# TT_PulseGen_V1_0.net
KiCad netlist of a schematic drawn in EAGLE
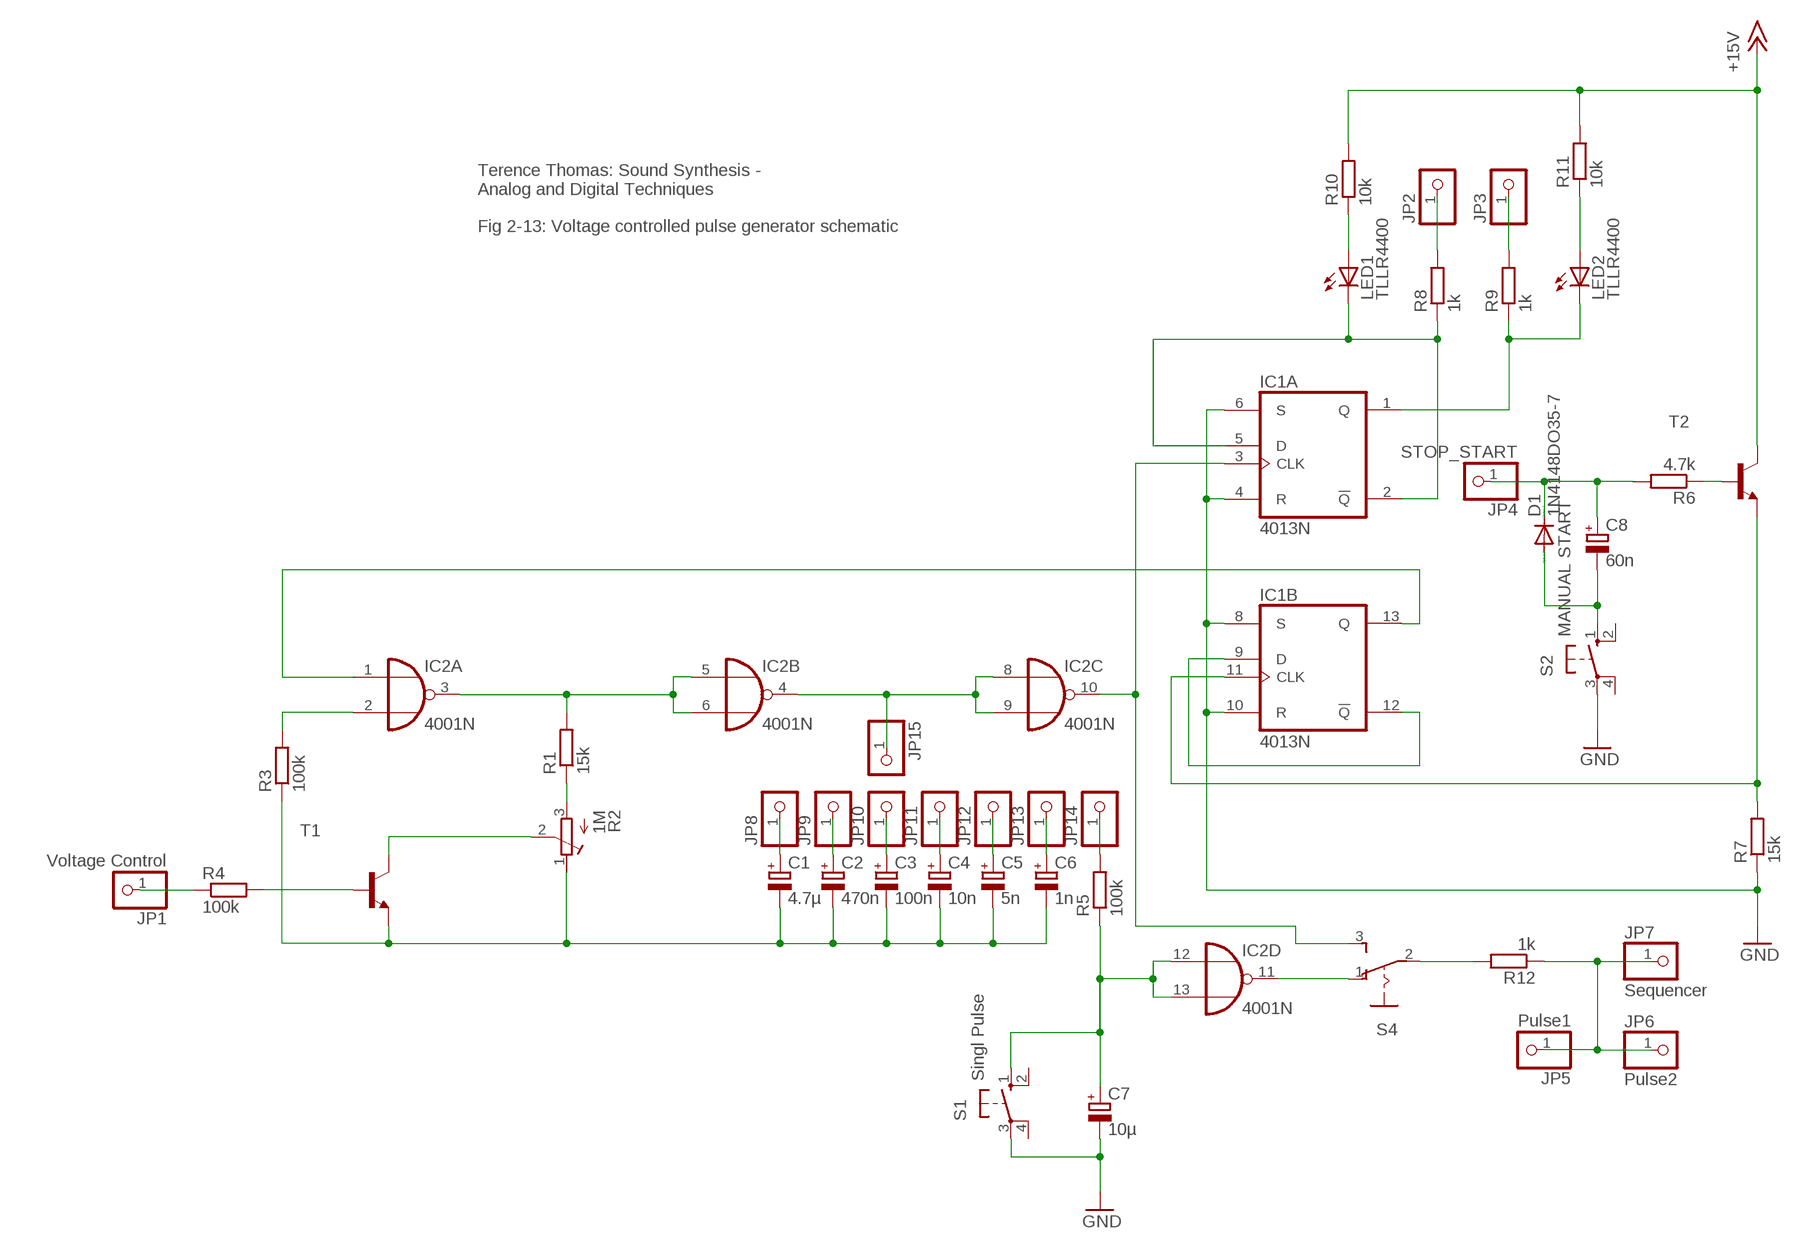
[diagram p0: schematic, sheet 1]

(export (version "E")
  (design (tool "Eeschema 10.0.6"))
  (components
    (comp (ref "C1")
      (value "4.7µ")
      (footprint "eagle-import:E2,5-5")
      (libsource (lib "eagle-import") (part "CPOL-EUE2.5-5"))
    )
    (comp (ref "C2")
      (value "470n")
      (footprint "eagle-import:E2,5-5")
      (libsource (lib "eagle-import") (part "CPOL-EUE2.5-5"))
    )
    (comp (ref "C3")
      (value "100n")
      (footprint "eagle-import:E2,5-5")
      (libsource (lib "eagle-import") (part "CPOL-EUE2.5-5"))
    )
    (comp (ref "C4")
      (value "10n")
      (footprint "eagle-import:E2,5-5")
      (libsource (lib "eagle-import") (part "CPOL-EUE2.5-5"))
    )
    (comp (ref "C5")
      (value "5n")
      (footprint "eagle-import:E2,5-5")
      (libsource (lib "eagle-import") (part "CPOL-EUE2.5-5"))
    )
    (comp (ref "C6")
      (value "1n")
      (footprint "eagle-import:E2,5-5")
      (libsource (lib "eagle-import") (part "CPOL-EUE2.5-5"))
    )
    (comp (ref "C7")
      (value "10µ")
      (footprint "eagle-import:E2,5-5")
      (libsource (lib "eagle-import") (part "CPOL-EUE2.5-5"))
    )
    (comp (ref "C8")
      (value "60n")
      (footprint "eagle-import:E2,5-5")
      (libsource (lib "eagle-import") (part "CPOL-EUE2.5-5"))
    )
    (comp (ref "D1")
      (value "1N4148DO35-7")
      (footprint "eagle-import:DO35-7")
      (libsource (lib "eagle-import") (part "1N4148DO35-7"))
    )
    (comp (ref "IC1")
      (value "4013N")
      (footprint "eagle-import:DIL14")
      (libsource (lib "eagle-import") (part "4013N"))
    )
    (comp (ref "IC2")
      (value "4001N")
      (footprint "eagle-import:DIL14")
      (libsource (lib "eagle-import") (part "4001N"))
    )
    (comp (ref "JP1")
      (value "Voltage Control")
      (footprint "eagle-import:1X01")
      (libsource (lib "eagle-import") (part "PINHD-1X1"))
    )
    (comp (ref "JP2")
      (value "PINHD-1X1")
      (footprint "eagle-import:1X01")
      (libsource (lib "eagle-import") (part "PINHD-1X1"))
    )
    (comp (ref "JP3")
      (value "PINHD-1X1")
      (footprint "eagle-import:1X01")
      (libsource (lib "eagle-import") (part "PINHD-1X1"))
    )
    (comp (ref "JP4")
      (value "STOP_START")
      (footprint "eagle-import:1X01")
      (libsource (lib "eagle-import") (part "PINHD-1X1"))
    )
    (comp (ref "JP5")
      (value "Pulse1")
      (footprint "eagle-import:1X01")
      (libsource (lib "eagle-import") (part "PINHD-1X1"))
    )
    (comp (ref "JP6")
      (value "Pulse2")
      (footprint "eagle-import:1X01")
      (libsource (lib "eagle-import") (part "PINHD-1X1"))
    )
    (comp (ref "JP7")
      (value "Sequencer")
      (footprint "eagle-import:1X01")
      (libsource (lib "eagle-import") (part "PINHD-1X1"))
    )
    (comp (ref "JP8")
      (value "PINHD-1X1")
      (footprint "eagle-import:1X01")
      (libsource (lib "eagle-import") (part "PINHD-1X1"))
    )
    (comp (ref "JP9")
      (value "PINHD-1X1")
      (footprint "eagle-import:1X01")
      (libsource (lib "eagle-import") (part "PINHD-1X1"))
    )
    (comp (ref "JP10")
      (value "PINHD-1X1")
      (footprint "eagle-import:1X01")
      (libsource (lib "eagle-import") (part "PINHD-1X1"))
    )
    (comp (ref "JP11")
      (value "PINHD-1X1")
      (footprint "eagle-import:1X01")
      (libsource (lib "eagle-import") (part "PINHD-1X1"))
    )
    (comp (ref "JP12")
      (value "PINHD-1X1")
      (footprint "eagle-import:1X01")
      (libsource (lib "eagle-import") (part "PINHD-1X1"))
    )
    (comp (ref "JP13")
      (value "PINHD-1X1")
      (footprint "eagle-import:1X01")
      (libsource (lib "eagle-import") (part "PINHD-1X1"))
    )
    (comp (ref "JP14")
      (value "PINHD-1X1")
      (footprint "eagle-import:1X01")
      (libsource (lib "eagle-import") (part "PINHD-1X1"))
    )
    (comp (ref "JP15")
      (value "PINHD-1X1")
      (footprint "eagle-import:1X01")
      (libsource (lib "eagle-import") (part "PINHD-1X1"))
    )
    (comp (ref "LED1")
      (value "TLLR4400")
      (footprint "eagle-import:LED3MM")
      (fields (field (name "MF") "VISHAY SEMICONDUCTOR"))
      (libsource (lib "eagle-import") (part "TLLR4400"))
    )
    (comp (ref "LED2")
      (value "TLLR4400")
      (footprint "eagle-import:LED3MM")
      (fields (field (name "MF") "VISHAY SEMICONDUCTOR"))
      (libsource (lib "eagle-import") (part "TLLR4400"))
    )
    (comp (ref "R1")
      (value "15k")
      (footprint "eagle-import:0204_7")
      (libsource (lib "eagle-import") (part "R-EU_0204/7"))
    )
    (comp (ref "R2")
      (value "1M")
      (footprint "eagle-import:RTRIMT93YA")
      (libsource (lib "eagle-import") (part "R-TRIMMT93YA"))
    )
    (comp (ref "R3")
      (value "100k")
      (footprint "eagle-import:0204_7")
      (libsource (lib "eagle-import") (part "R-EU_0204/7"))
    )
    (comp (ref "R4")
      (value "100k")
      (footprint "eagle-import:0204_7")
      (libsource (lib "eagle-import") (part "R-EU_0204/7"))
    )
    (comp (ref "R5")
      (value "100k")
      (footprint "eagle-import:0204_7")
      (libsource (lib "eagle-import") (part "R-EU_0204/7"))
    )
    (comp (ref "R6")
      (value "4.7k")
      (footprint "eagle-import:0204_7")
      (libsource (lib "eagle-import") (part "R-EU_0204/7"))
    )
    (comp (ref "R7")
      (value "15k")
      (footprint "eagle-import:0204_7")
      (libsource (lib "eagle-import") (part "R-EU_0204/7"))
    )
    (comp (ref "R8")
      (value "1k")
      (footprint "eagle-import:0204_7")
      (libsource (lib "eagle-import") (part "R-EU_0204/7"))
    )
    (comp (ref "R9")
      (value "1k")
      (footprint "eagle-import:0204_7")
      (libsource (lib "eagle-import") (part "R-EU_0204/7"))
    )
    (comp (ref "R10")
      (value "10k")
      (footprint "eagle-import:0204_7")
      (libsource (lib "eagle-import") (part "R-EU_0204/7"))
    )
    (comp (ref "R11")
      (value "10k")
      (footprint "eagle-import:0204_7")
      (libsource (lib "eagle-import") (part "R-EU_0204/7"))
    )
    (comp (ref "R12")
      (value "1k")
      (footprint "eagle-import:0204_7")
      (libsource (lib "eagle-import") (part "R-EU_0204/7"))
    )
    (comp (ref "S1")
      (value "Singl Pulse")
      (footprint "eagle-import:B3F-10XX")
      (fields (field (name "MPN") "B3F-1000"))
      (libsource (lib "eagle-import") (part "10-XX"))
    )
    (comp (ref "S2")
      (value "MANUAL START")
      (footprint "eagle-import:B3F-10XX")
      (fields (field (name "MPN") "B3F-1000"))
      (libsource (lib "eagle-import") (part "10-XX"))
    )
    (comp (ref "S4")
      (value "255SB")
      (footprint "eagle-import:255SB")
      (libsource (lib "eagle-import") (part "255SB"))
    )
    (comp (ref "T1")
      (value "-NPN-TO92-EBC")
      (footprint "eagle-import:TO92-EBC")
      (libsource (lib "eagle-import") (part "-NPN-TO92-EBC"))
    )
    (comp (ref "T2")
      (value "-NPN-TO92-EBC")
      (footprint "eagle-import:TO92-EBC")
      (libsource (lib "eagle-import") (part "-NPN-TO92-EBC"))
    )
  )
  (nets
    (net (code "1") (name "+15V") (class "Default")
      (node (ref "R10") (pin "2") (pinfunction "2_2") (pintype "passive"))
      (node (ref "R11") (pin "2") (pinfunction "2_2") (pintype "passive"))
      (node (ref "T2") (pin "C") (pinfunction "C_C") (pintype "passive"))
    )
    (net (code "2") (name "GND") (class "Default")
      (node (ref "C7") (pin "-") (pinfunction "-_-") (pintype "passive"))
      (node (ref "IC1") (pin "10") (pinfunction "R_10") (pintype "input"))
      (node (ref "IC1") (pin "4") (pinfunction "R_4") (pintype "input"))
      (node (ref "IC1") (pin "6") (pinfunction "S_6") (pintype "input"))
      (node (ref "IC1") (pin "8") (pinfunction "S_8") (pintype "input"))
      (node (ref "R7") (pin "1") (pinfunction "1_1") (pintype "passive"))
      (node (ref "S1") (pin "3") (pinfunction "P_3") (pintype "passive"))
      (node (ref "S2") (pin "3") (pinfunction "P_3") (pintype "passive"))
    )
    (net (code "3") (name "Net-(C1-Pad+)") (class "Default")
      (node (ref "C1") (pin "+") (pinfunction "+_+") (pintype "passive"))
      (node (ref "JP8") (pin "1") (pinfunction "1_1") (pintype "passive"))
    )
    (net (code "4") (name "Net-(C2-Pad+)") (class "Default")
      (node (ref "C2") (pin "+") (pinfunction "+_+") (pintype "passive"))
      (node (ref "JP9") (pin "1") (pinfunction "1_1") (pintype "passive"))
    )
    (net (code "5") (name "Net-(C3-Pad+)") (class "Default")
      (node (ref "C3") (pin "+") (pinfunction "+_+") (pintype "passive"))
      (node (ref "JP10") (pin "1") (pinfunction "1_1") (pintype "passive"))
    )
    (net (code "6") (name "Net-(C4-Pad+)") (class "Default")
      (node (ref "C4") (pin "+") (pinfunction "+_+") (pintype "passive"))
      (node (ref "JP11") (pin "1") (pinfunction "1_1") (pintype "passive"))
    )
    (net (code "7") (name "Net-(C5-Pad+)") (class "Default")
      (node (ref "C5") (pin "+") (pinfunction "+_+") (pintype "passive"))
      (node (ref "JP12") (pin "1") (pinfunction "1_1") (pintype "passive"))
    )
    (net (code "8") (name "Net-(C6-Pad+)") (class "Default")
      (node (ref "C6") (pin "+") (pinfunction "+_+") (pintype "passive"))
      (node (ref "JP13") (pin "1") (pinfunction "1_1") (pintype "passive"))
    )
    (net (code "9") (name "Net-(C8-Pad+)") (class "Default")
      (node (ref "C8") (pin "+") (pinfunction "+_+") (pintype "passive"))
      (node (ref "D1") (pin "C") (pinfunction "C_C") (pintype "passive"))
      (node (ref "JP4") (pin "1") (pinfunction "1_1") (pintype "passive"))
      (node (ref "R6") (pin "2") (pinfunction "2_2") (pintype "passive"))
    )
    (net (code "10") (name "Net-(IC1A-CLK)") (class "Default")
      (node (ref "IC1") (pin "3") (pinfunction "CLK_3") (pintype "input"))
      (node (ref "IC2") (pin "10") (pinfunction "O_10") (pintype "output"))
      (node (ref "S4") (pin "3") (pinfunction "S_3") (pintype "passive"))
    )
    (net (code "11") (name "Net-(IC1A-D)") (class "Default")
      (node (ref "IC1") (pin "2") (pinfunction "~{Q}_2") (pintype "output"))
      (node (ref "IC1") (pin "5") (pinfunction "D_5") (pintype "input"))
      (node (ref "LED1") (pin "K") (pinfunction "C_K") (pintype "passive"))
      (node (ref "R8") (pin "1") (pinfunction "1_1") (pintype "passive"))
    )
    (net (code "12") (name "Net-(IC1A-Q)") (class "Default")
      (node (ref "IC1") (pin "1") (pinfunction "Q_1") (pintype "output"))
      (node (ref "LED2") (pin "K") (pinfunction "C_K") (pintype "passive"))
      (node (ref "R9") (pin "1") (pinfunction "1_1") (pintype "passive"))
    )
    (net (code "13") (name "Net-(IC1B-CLK)") (class "Default")
      (node (ref "IC1") (pin "11") (pinfunction "CLK_11") (pintype "input"))
      (node (ref "R7") (pin "2") (pinfunction "2_2") (pintype "passive"))
      (node (ref "T2") (pin "E") (pinfunction "E_E") (pintype "passive"))
    )
    (net (code "14") (name "Net-(IC1B-D)") (class "Default")
      (node (ref "IC1") (pin "12") (pinfunction "~{Q}_12") (pintype "output"))
      (node (ref "IC1") (pin "9") (pinfunction "D_9") (pintype "input"))
    )
    (net (code "15") (name "Net-(IC1B-Q)") (class "Default")
      (node (ref "IC1") (pin "13") (pinfunction "Q_13") (pintype "output"))
      (node (ref "IC2") (pin "1") (pinfunction "I0_1") (pintype "input"))
    )
    (net (code "16") (name "Net-(IC2A-I1)") (class "Default")
      (node (ref "IC2") (pin "2") (pinfunction "I1_2") (pintype "input"))
      (node (ref "R3") (pin "2") (pinfunction "2_2") (pintype "passive"))
    )
    (net (code "17") (name "Net-(IC2A-O)") (class "Default")
      (node (ref "IC2") (pin "3") (pinfunction "O_3") (pintype "output"))
      (node (ref "IC2") (pin "5") (pinfunction "I0_5") (pintype "input"))
      (node (ref "IC2") (pin "6") (pinfunction "I1_6") (pintype "input"))
      (node (ref "R1") (pin "2") (pinfunction "2_2") (pintype "passive"))
    )
    (net (code "18") (name "Net-(IC2B-O)") (class "Default")
      (node (ref "IC2") (pin "4") (pinfunction "O_4") (pintype "output"))
      (node (ref "IC2") (pin "8") (pinfunction "I0_8") (pintype "input"))
      (node (ref "IC2") (pin "9") (pinfunction "I1_9") (pintype "input"))
      (node (ref "JP15") (pin "1") (pinfunction "1_1") (pintype "passive"))
    )
    (net (code "19") (name "Net-(IC2D-I0)") (class "Default")
      (node (ref "C7") (pin "+") (pinfunction "+_+") (pintype "passive"))
      (node (ref "IC2") (pin "12") (pinfunction "I0_12") (pintype "input"))
      (node (ref "IC2") (pin "13") (pinfunction "I1_13") (pintype "input"))
      (node (ref "R5") (pin "1") (pinfunction "1_1") (pintype "passive"))
      (node (ref "S1") (pin "1") (pinfunction "S_1") (pintype "passive"))
    )
    (net (code "20") (name "Net-(IC2D-O)") (class "Default")
      (node (ref "IC2") (pin "11") (pinfunction "O_11") (pintype "output"))
      (node (ref "S4") (pin "1") (pinfunction "O_1") (pintype "passive"))
    )
    (net (code "21") (name "Net-(JP1-Pad1)") (class "Default")
      (node (ref "JP1") (pin "1") (pinfunction "1_1") (pintype "passive"))
      (node (ref "R4") (pin "1") (pinfunction "1_1") (pintype "passive"))
    )
    (net (code "22") (name "Net-(JP2-Pad1)") (class "Default")
      (node (ref "JP2") (pin "1") (pinfunction "1_1") (pintype "passive"))
      (node (ref "R8") (pin "2") (pinfunction "2_2") (pintype "passive"))
    )
    (net (code "23") (name "Net-(JP3-Pad1)") (class "Default")
      (node (ref "JP3") (pin "1") (pinfunction "1_1") (pintype "passive"))
      (node (ref "R9") (pin "2") (pinfunction "2_2") (pintype "passive"))
    )
    (net (code "24") (name "Net-(JP5-Pad1)") (class "Default")
      (node (ref "JP5") (pin "1") (pinfunction "1_1") (pintype "passive"))
      (node (ref "JP6") (pin "1") (pinfunction "1_1") (pintype "passive"))
      (node (ref "JP7") (pin "1") (pinfunction "1_1") (pintype "passive"))
      (node (ref "R12") (pin "1") (pinfunction "1_1") (pintype "passive"))
    )
    (net (code "25") (name "Net-(JP14-Pad1)") (class "Default")
      (node (ref "JP14") (pin "1") (pinfunction "1_1") (pintype "passive"))
      (node (ref "R5") (pin "2") (pinfunction "2_2") (pintype "passive"))
    )
    (net (code "26") (name "Net-(LED1-PadA)") (class "Default")
      (node (ref "LED1") (pin "A") (pinfunction "A_A") (pintype "passive"))
      (node (ref "R10") (pin "1") (pinfunction "1_1") (pintype "passive"))
    )
    (net (code "27") (name "Net-(LED2-PadA)") (class "Default")
      (node (ref "LED2") (pin "A") (pinfunction "A_A") (pintype "passive"))
      (node (ref "R11") (pin "1") (pinfunction "1_1") (pintype "passive"))
    )
    (net (code "28") (name "Net-(R2-A)") (class "Default")
      (node (ref "R1") (pin "1") (pinfunction "1_1") (pintype "passive"))
      (node (ref "R2") (pin "3") (pinfunction "A_3") (pintype "passive"))
    )
    (net (code "29") (name "Net-(R2-E)") (class "Default")
      (node (ref "C1") (pin "-") (pinfunction "-_-") (pintype "passive"))
      (node (ref "C2") (pin "-") (pinfunction "-_-") (pintype "passive"))
      (node (ref "C3") (pin "-") (pinfunction "-_-") (pintype "passive"))
      (node (ref "C4") (pin "-") (pinfunction "-_-") (pintype "passive"))
      (node (ref "C5") (pin "-") (pinfunction "-_-") (pintype "passive"))
      (node (ref "C6") (pin "-") (pinfunction "-_-") (pintype "passive"))
      (node (ref "R2") (pin "1") (pinfunction "E_1") (pintype "passive"))
      (node (ref "R3") (pin "1") (pinfunction "1_1") (pintype "passive"))
      (node (ref "T1") (pin "E") (pinfunction "E_E") (pintype "passive"))
    )
    (net (code "30") (name "Net-(R2-S)") (class "Default")
      (node (ref "R2") (pin "2") (pinfunction "S_2") (pintype "passive"))
      (node (ref "T1") (pin "C") (pinfunction "C_C") (pintype "passive"))
    )
    (net (code "31") (name "Net-(R4-Pad2)") (class "Default")
      (node (ref "R4") (pin "2") (pinfunction "2_2") (pintype "passive"))
      (node (ref "T1") (pin "B") (pinfunction "B_B") (pintype "passive"))
    )
    (net (code "32") (name "Net-(R6-Pad1)") (class "Default")
      (node (ref "R6") (pin "1") (pinfunction "1_1") (pintype "passive"))
      (node (ref "T2") (pin "B") (pinfunction "B_B") (pintype "passive"))
    )
    (net (code "33") (name "Net-(S2-S)") (class "Default")
      (node (ref "C8") (pin "-") (pinfunction "-_-") (pintype "passive"))
      (node (ref "D1") (pin "A") (pinfunction "A_A") (pintype "passive"))
      (node (ref "S2") (pin "1") (pinfunction "S_1") (pintype "passive"))
    )
    (net (code "34") (name "Net-(S4-P)") (class "Default")
      (node (ref "R12") (pin "2") (pinfunction "2_2") (pintype "passive"))
      (node (ref "S4") (pin "2") (pinfunction "P_2") (pintype "passive"))
    )
    (net (code "35") (name "unconnected-(S1-P1-Pad4)") (class "Default")
      (node (ref "S1") (pin "4") (pinfunction "P1_4") (pintype "passive"))
    )
    (net (code "36") (name "unconnected-(S1-S1-Pad2)") (class "Default")
      (node (ref "S1") (pin "2") (pinfunction "S1_2") (pintype "passive"))
    )
    (net (code "37") (name "unconnected-(S2-P1-Pad4)") (class "Default")
      (node (ref "S2") (pin "4") (pinfunction "P1_4") (pintype "passive"))
    )
    (net (code "38") (name "unconnected-(S2-S1-Pad2)") (class "Default")
      (node (ref "S2") (pin "2") (pinfunction "S1_2") (pintype "passive"))
    )
  )
)
